# X_V1_0_4040Lite.net
KiCad netlist of a schematic drawn in EasyEDA Pro
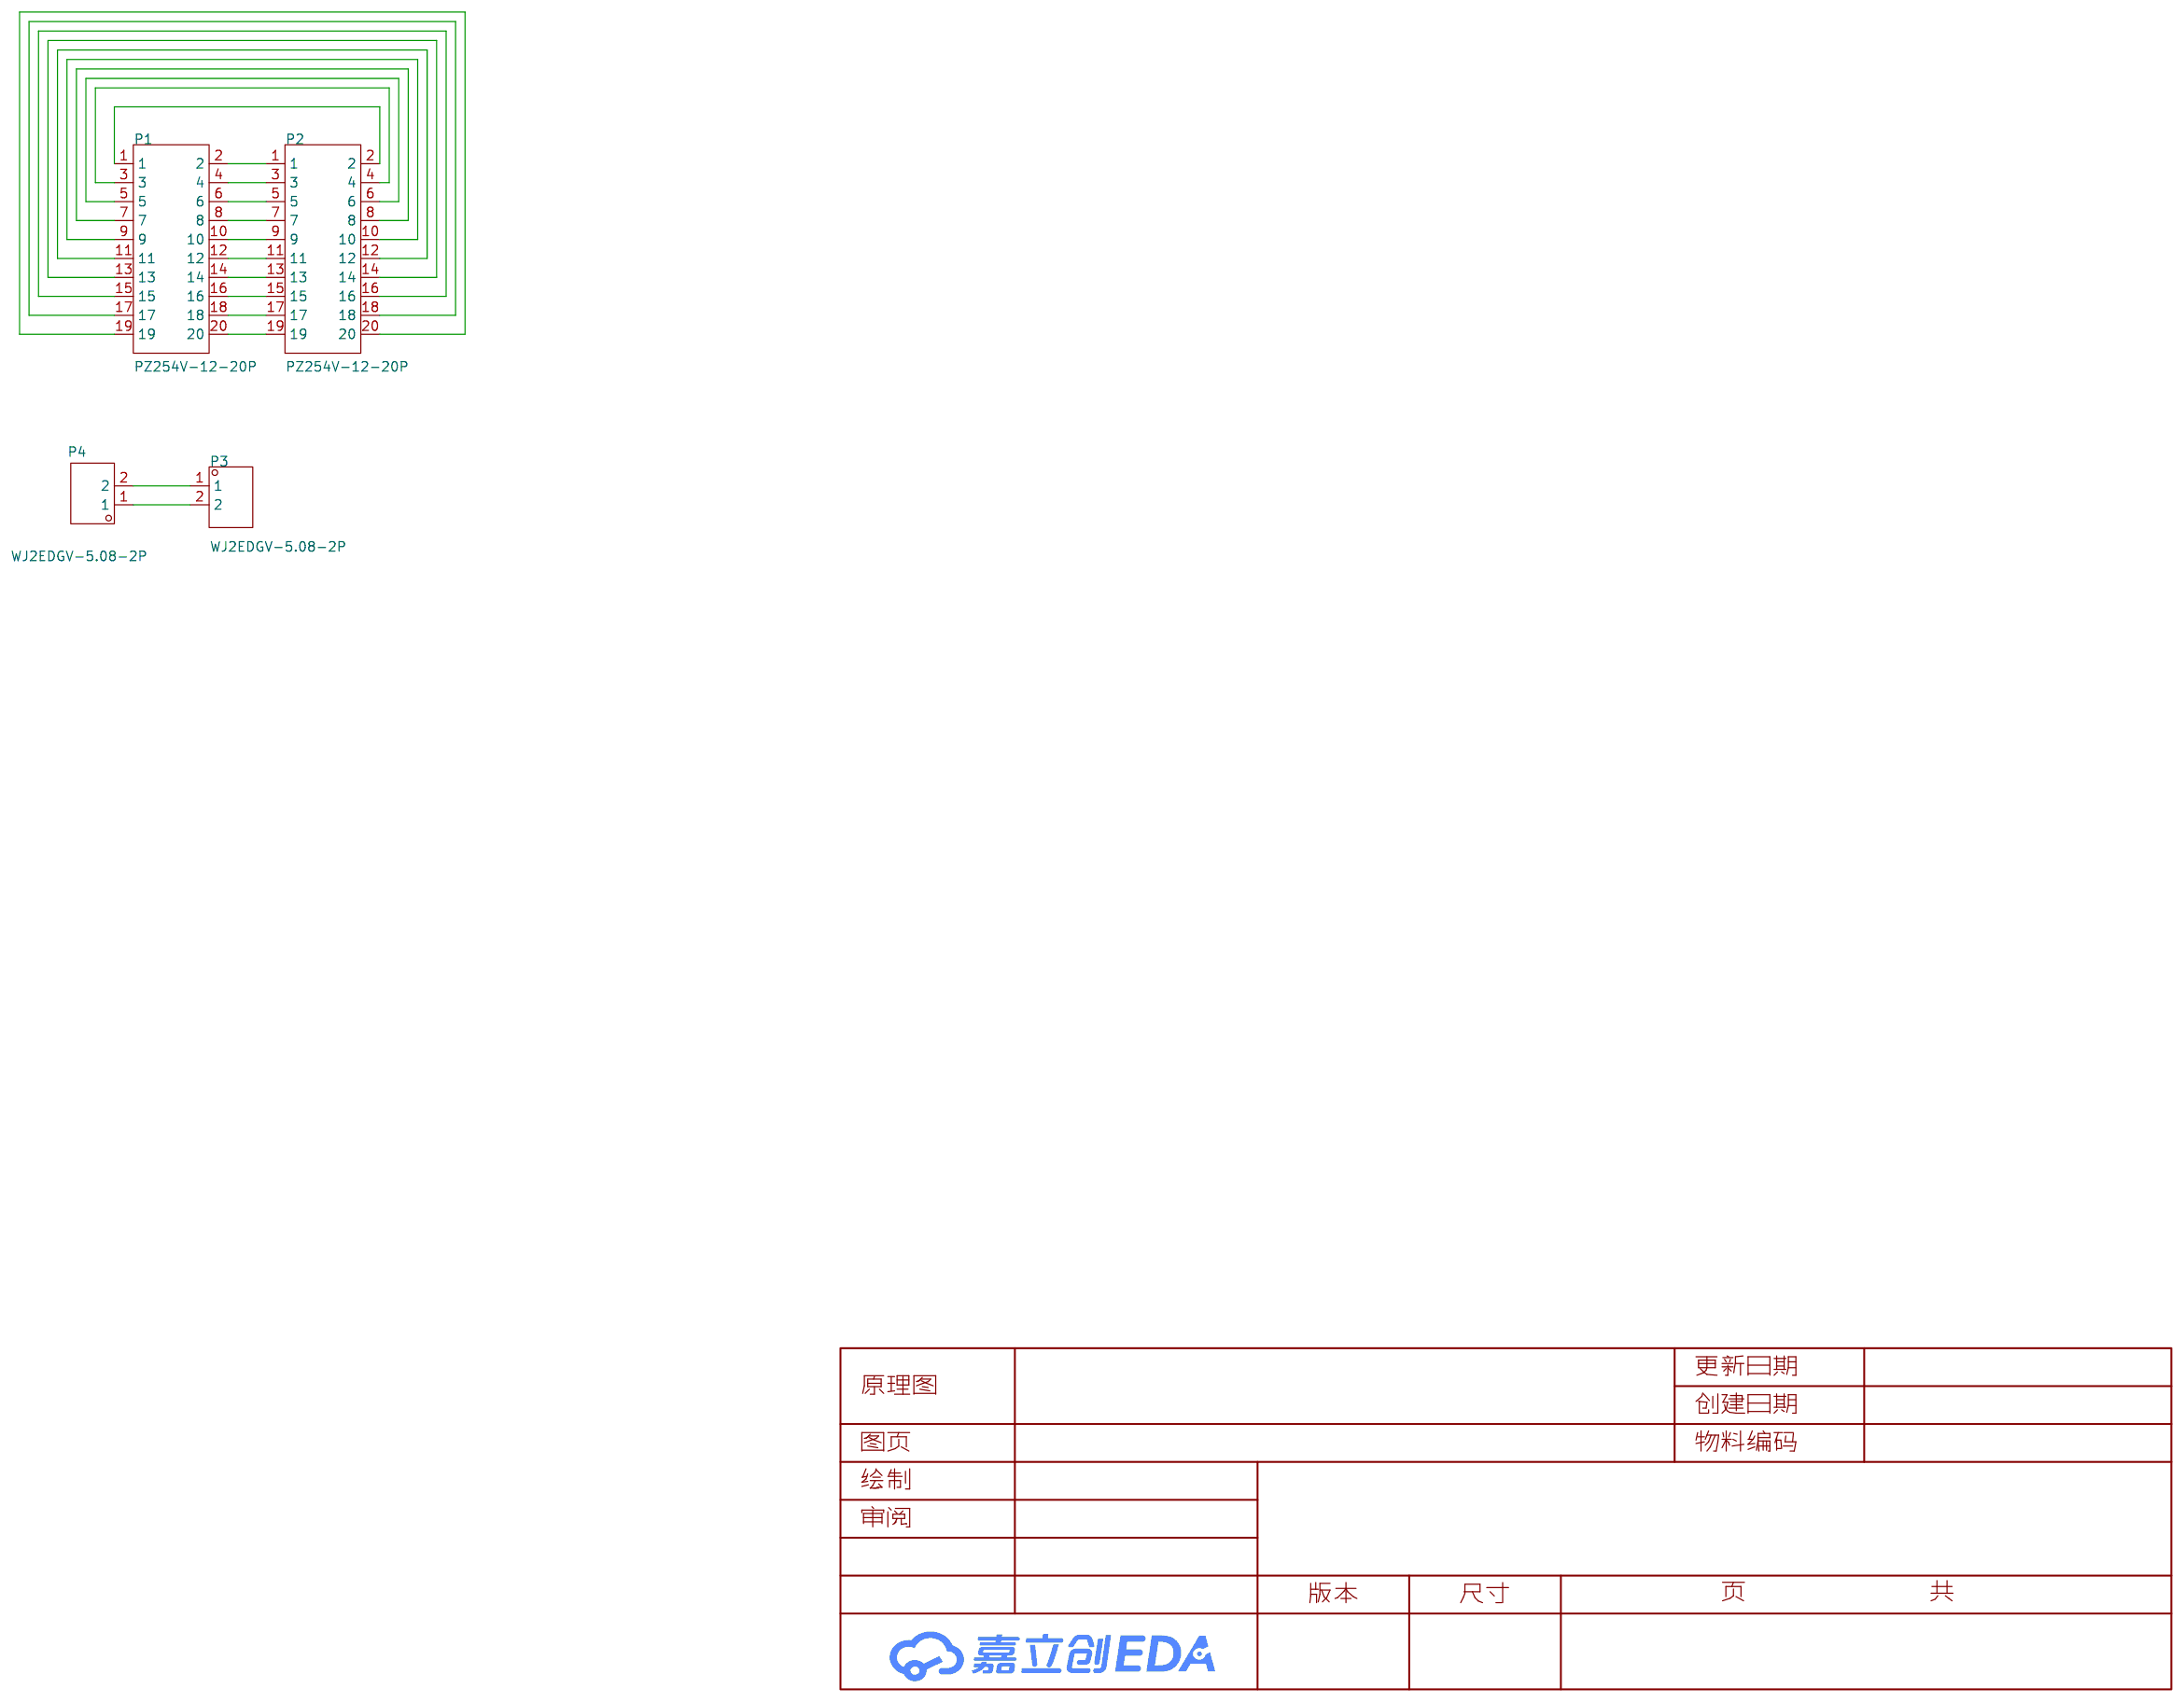
[diagram p0: schematic sheet]

(export (version "E")
  (design (tool "Eeschema 10.0.6"))
  (components
    (comp (ref "P1")
      (value "PZ254V-12-20P")
      (footprint "easyedapro:HDR-TH_20P-P2.54-V-M-R2-C10-S2.54")
      (fields (field (name "Manufacturer") "XFCN(兴飞)"))
      (libsource (lib "easyedapro") (part "PZ254V-12-20P"))
    )
    (comp (ref "P2")
      (value "PZ254V-12-20P")
      (footprint "easyedapro:HDR-TH_20P-P2.54-V-M-R2-C10-S2.54")
      (fields (field (name "Manufacturer") "XFCN(兴飞)"))
      (libsource (lib "easyedapro") (part "PZ254V-12-20P"))
    )
    (comp (ref "P3")
      (value "WJ2EDGV-5.08-2P")
      (footprint "easyedapro:CONN-TH_WJ2EDGV-5.08-2P")
      (fields (field (name "Manufacturer") "KANGNEX(康奈克斯电气)"))
      (libsource (lib "easyedapro") (part "WJ2EDGV-5.08-2P"))
    )
    (comp (ref "P4")
      (value "WJ2EDGV-5.08-2P")
      (footprint "easyedapro:CONN-TH_WJ2EDGV-5.08-2P")
      (fields (field (name "Manufacturer") "KANGNEX(康奈克斯电气)"))
      (libsource (lib "easyedapro") (part "WJ2EDGV-5.08-2P"))
    )
  )
  (nets
    (net (code "1") (name "Net-(P1-Pad1)") (class "Default")
      (node (ref "P1") (pin "1") (pinfunction "1_1") (pintype "unspecified"))
      (node (ref "P2") (pin "2") (pinfunction "2_2") (pintype "unspecified"))
    )
    (net (code "2") (name "Net-(P1-Pad2)") (class "Default")
      (node (ref "P1") (pin "2") (pinfunction "2_2") (pintype "unspecified"))
      (node (ref "P2") (pin "1") (pinfunction "1_1") (pintype "unspecified"))
    )
    (net (code "3") (name "Net-(P1-Pad3)") (class "Default")
      (node (ref "P1") (pin "3") (pinfunction "3_3") (pintype "unspecified"))
      (node (ref "P2") (pin "4") (pinfunction "4_4") (pintype "unspecified"))
    )
    (net (code "4") (name "Net-(P1-Pad4)") (class "Default")
      (node (ref "P1") (pin "4") (pinfunction "4_4") (pintype "unspecified"))
      (node (ref "P2") (pin "3") (pinfunction "3_3") (pintype "unspecified"))
    )
    (net (code "5") (name "Net-(P1-Pad5)") (class "Default")
      (node (ref "P1") (pin "5") (pinfunction "5_5") (pintype "unspecified"))
      (node (ref "P2") (pin "6") (pinfunction "6_6") (pintype "unspecified"))
    )
    (net (code "6") (name "Net-(P1-Pad6)") (class "Default")
      (node (ref "P1") (pin "6") (pinfunction "6_6") (pintype "unspecified"))
      (node (ref "P2") (pin "5") (pinfunction "5_5") (pintype "unspecified"))
    )
    (net (code "7") (name "Net-(P1-Pad7)") (class "Default")
      (node (ref "P1") (pin "7") (pinfunction "7_7") (pintype "unspecified"))
      (node (ref "P2") (pin "8") (pinfunction "8_8") (pintype "unspecified"))
    )
    (net (code "8") (name "Net-(P1-Pad8)") (class "Default")
      (node (ref "P1") (pin "8") (pinfunction "8_8") (pintype "unspecified"))
      (node (ref "P2") (pin "7") (pinfunction "7_7") (pintype "unspecified"))
    )
    (net (code "9") (name "Net-(P1-Pad9)") (class "Default")
      (node (ref "P1") (pin "9") (pinfunction "9_9") (pintype "unspecified"))
      (node (ref "P2") (pin "10") (pinfunction "10_10") (pintype "unspecified"))
    )
    (net (code "10") (name "Net-(P1-Pad10)") (class "Default")
      (node (ref "P1") (pin "10") (pinfunction "10_10") (pintype "unspecified"))
      (node (ref "P2") (pin "9") (pinfunction "9_9") (pintype "unspecified"))
    )
    (net (code "11") (name "Net-(P1-Pad11)") (class "Default")
      (node (ref "P1") (pin "11") (pinfunction "11_11") (pintype "unspecified"))
      (node (ref "P2") (pin "12") (pinfunction "12_12") (pintype "unspecified"))
    )
    (net (code "12") (name "Net-(P1-Pad12)") (class "Default")
      (node (ref "P1") (pin "12") (pinfunction "12_12") (pintype "unspecified"))
      (node (ref "P2") (pin "11") (pinfunction "11_11") (pintype "unspecified"))
    )
    (net (code "13") (name "Net-(P1-Pad13)") (class "Default")
      (node (ref "P1") (pin "13") (pinfunction "13_13") (pintype "unspecified"))
      (node (ref "P2") (pin "14") (pinfunction "14_14") (pintype "unspecified"))
    )
    (net (code "14") (name "Net-(P1-Pad14)") (class "Default")
      (node (ref "P1") (pin "14") (pinfunction "14_14") (pintype "unspecified"))
      (node (ref "P2") (pin "13") (pinfunction "13_13") (pintype "unspecified"))
    )
    (net (code "15") (name "Net-(P1-Pad15)") (class "Default")
      (node (ref "P1") (pin "15") (pinfunction "15_15") (pintype "unspecified"))
      (node (ref "P2") (pin "16") (pinfunction "16_16") (pintype "unspecified"))
    )
    (net (code "16") (name "Net-(P1-Pad16)") (class "Default")
      (node (ref "P1") (pin "16") (pinfunction "16_16") (pintype "unspecified"))
      (node (ref "P2") (pin "15") (pinfunction "15_15") (pintype "unspecified"))
    )
    (net (code "17") (name "Net-(P1-Pad17)") (class "Default")
      (node (ref "P1") (pin "17") (pinfunction "17_17") (pintype "unspecified"))
      (node (ref "P2") (pin "18") (pinfunction "18_18") (pintype "unspecified"))
    )
    (net (code "18") (name "Net-(P1-Pad18)") (class "Default")
      (node (ref "P1") (pin "18") (pinfunction "18_18") (pintype "unspecified"))
      (node (ref "P2") (pin "17") (pinfunction "17_17") (pintype "unspecified"))
    )
    (net (code "19") (name "Net-(P1-Pad19)") (class "Default")
      (node (ref "P1") (pin "19") (pinfunction "19_19") (pintype "unspecified"))
      (node (ref "P2") (pin "20") (pinfunction "20_20") (pintype "unspecified"))
    )
    (net (code "20") (name "Net-(P1-Pad20)") (class "Default")
      (node (ref "P1") (pin "20") (pinfunction "20_20") (pintype "unspecified"))
      (node (ref "P2") (pin "19") (pinfunction "19_19") (pintype "unspecified"))
    )
    (net (code "21") (name "Net-(P3-Pad1)") (class "Default")
      (node (ref "P3") (pin "1") (pinfunction "1_1") (pintype "unspecified"))
      (node (ref "P4") (pin "2") (pinfunction "2_2") (pintype "unspecified"))
    )
    (net (code "22") (name "Net-(P3-Pad2)") (class "Default")
      (node (ref "P3") (pin "2") (pinfunction "2_2") (pintype "unspecified"))
      (node (ref "P4") (pin "1") (pinfunction "1_1") (pintype "unspecified"))
    )
  )
)
